# oc_oscillator.net
KiCad netlist of a schematic drawn in EAGLE
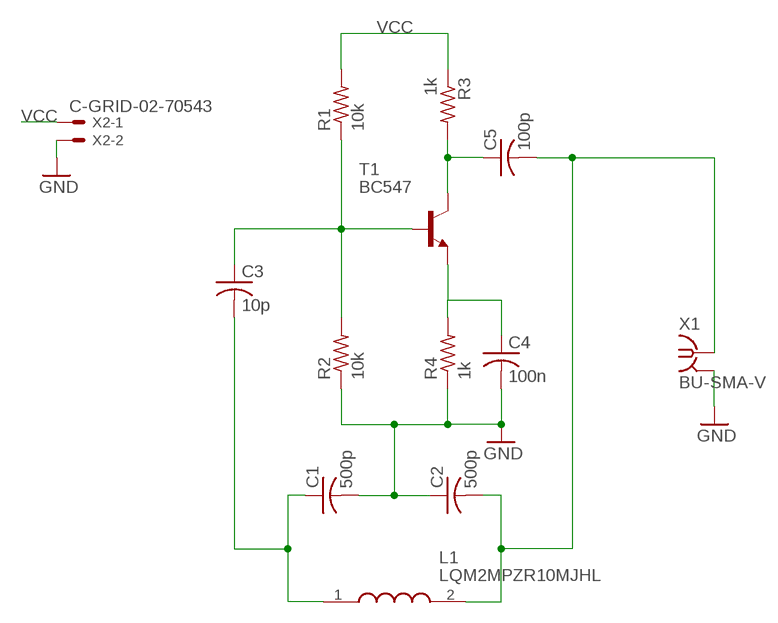
[diagram p0: schematic, sheet 1]

(export (version "E")
  (design (tool "Eeschema 10.0.6"))
  (components
    (comp (ref "C1")
      (value "500p")
      (footprint "eagle-import:C0805")
      (libsource (lib "eagle-import") (part "C-USC0805"))
    )
    (comp (ref "C2")
      (value "500p")
      (footprint "eagle-import:C0805")
      (libsource (lib "eagle-import") (part "C-USC0805"))
    )
    (comp (ref "C3")
      (value "10p")
      (footprint "eagle-import:C0805")
      (libsource (lib "eagle-import") (part "C-USC0805"))
    )
    (comp (ref "C4")
      (value "100n")
      (footprint "eagle-import:C0805")
      (libsource (lib "eagle-import") (part "C-USC0805"))
    )
    (comp (ref "C5")
      (value "100p")
      (footprint "eagle-import:C0805")
      (libsource (lib "eagle-import") (part "C-USC0805"))
    )
    (comp (ref "L1")
      (value "LQM2MPZR10MJHL")
      (footprint "eagle-import:INDC2016X120N")
      (fields (field (name "MOUSER_PART_NUMBER") "81-LQM2MPZR10MJHL"))
      (libsource (lib "eagle-import") (part "LQM2MPZR10MJHL"))
    )
    (comp (ref "R1")
      (value "10k")
      (footprint "eagle-import:M0805")
      (libsource (lib "eagle-import") (part "R-US_M0805"))
    )
    (comp (ref "R2")
      (value "10k")
      (footprint "eagle-import:M0805")
      (libsource (lib "eagle-import") (part "R-US_M0805"))
    )
    (comp (ref "R3")
      (value "1k")
      (footprint "eagle-import:M0805")
      (libsource (lib "eagle-import") (part "R-US_M0805"))
    )
    (comp (ref "R4")
      (value "1k")
      (footprint "eagle-import:M0805")
      (libsource (lib "eagle-import") (part "R-US_M0805"))
    )
    (comp (ref "T1")
      (value "BC547")
      (footprint "eagle-import:TO92")
      (libsource (lib "eagle-import") (part "BC547"))
    )
    (comp (ref "X1")
      (value "BU-SMA-V")
      (footprint "eagle-import:BU-SMA-V")
      (libsource (lib "eagle-import") (part "BU-SMA-V"))
    )
    (comp (ref "X2")
      (value "C-GRID-02-70543")
      (footprint "eagle-import:70543-02")
      (fields (field (name "MF") "MOLEX"))
      (libsource (lib "eagle-import") (part "C-GRID-02-70543"))
    )
  )
  (nets
    (net (code "1") (name "/VCC") (class "Default")
      (node (ref "R1") (pin "2") (pinfunction "2_2") (pintype "passive"))
      (node (ref "R3") (pin "1") (pinfunction "1_1") (pintype "passive"))
      (node (ref "X2") (pin "1") (pinfunction "S_1") (pintype "passive"))
    )
    (net (code "2") (name "GND") (class "Default")
      (node (ref "C1") (pin "2") (pinfunction "2_2") (pintype "passive"))
      (node (ref "C2") (pin "1") (pinfunction "1_1") (pintype "passive"))
      (node (ref "C4") (pin "2") (pinfunction "2_2") (pintype "passive"))
      (node (ref "R2") (pin "1") (pinfunction "1_1") (pintype "passive"))
      (node (ref "R4") (pin "1") (pinfunction "1_1") (pintype "passive"))
      (node (ref "X1") (pin "2") (pinfunction "2_2") (pintype "passive"))
      (node (ref "X1") (pin "3") (pinfunction "2_3") (pintype "passive"))
      (node (ref "X1") (pin "4") (pinfunction "2_4") (pintype "passive"))
      (node (ref "X1") (pin "5") (pinfunction "2_5") (pintype "passive"))
      (node (ref "X2") (pin "2") (pinfunction "S_2") (pintype "passive"))
    )
    (net (code "3") (name "Net-(C1-Pad1)") (class "Default")
      (node (ref "C1") (pin "1") (pinfunction "1_1") (pintype "passive"))
      (node (ref "C3") (pin "2") (pinfunction "2_2") (pintype "passive"))
      (node (ref "L1") (pin "1") (pinfunction "1_1") (pintype "bidirectional"))
    )
    (net (code "4") (name "Net-(C2-Pad2)") (class "Default")
      (node (ref "C2") (pin "2") (pinfunction "2_2") (pintype "passive"))
      (node (ref "C5") (pin "2") (pinfunction "2_2") (pintype "passive"))
      (node (ref "L1") (pin "2") (pinfunction "2_2") (pintype "bidirectional"))
      (node (ref "X1") (pin "1") (pinfunction "1_1") (pintype "passive"))
    )
    (net (code "5") (name "Net-(T1-B)") (class "Default")
      (node (ref "C3") (pin "1") (pinfunction "1_1") (pintype "passive"))
      (node (ref "R1") (pin "1") (pinfunction "1_1") (pintype "passive"))
      (node (ref "R2") (pin "2") (pinfunction "2_2") (pintype "passive"))
      (node (ref "T1") (pin "2") (pinfunction "B_2") (pintype "passive"))
    )
    (net (code "6") (name "Net-(T1-C)") (class "Default")
      (node (ref "C5") (pin "1") (pinfunction "1_1") (pintype "passive"))
      (node (ref "R3") (pin "2") (pinfunction "2_2") (pintype "passive"))
      (node (ref "T1") (pin "3") (pinfunction "C_3") (pintype "passive"))
    )
    (net (code "7") (name "Net-(T1-E)") (class "Default")
      (node (ref "C4") (pin "1") (pinfunction "1_1") (pintype "passive"))
      (node (ref "R4") (pin "2") (pinfunction "2_2") (pintype "passive"))
      (node (ref "T1") (pin "1") (pinfunction "E_1") (pintype "passive"))
    )
  )
)
